# Tri-color_LED_Breakout.net
KiCad netlist of a schematic drawn in EAGLE
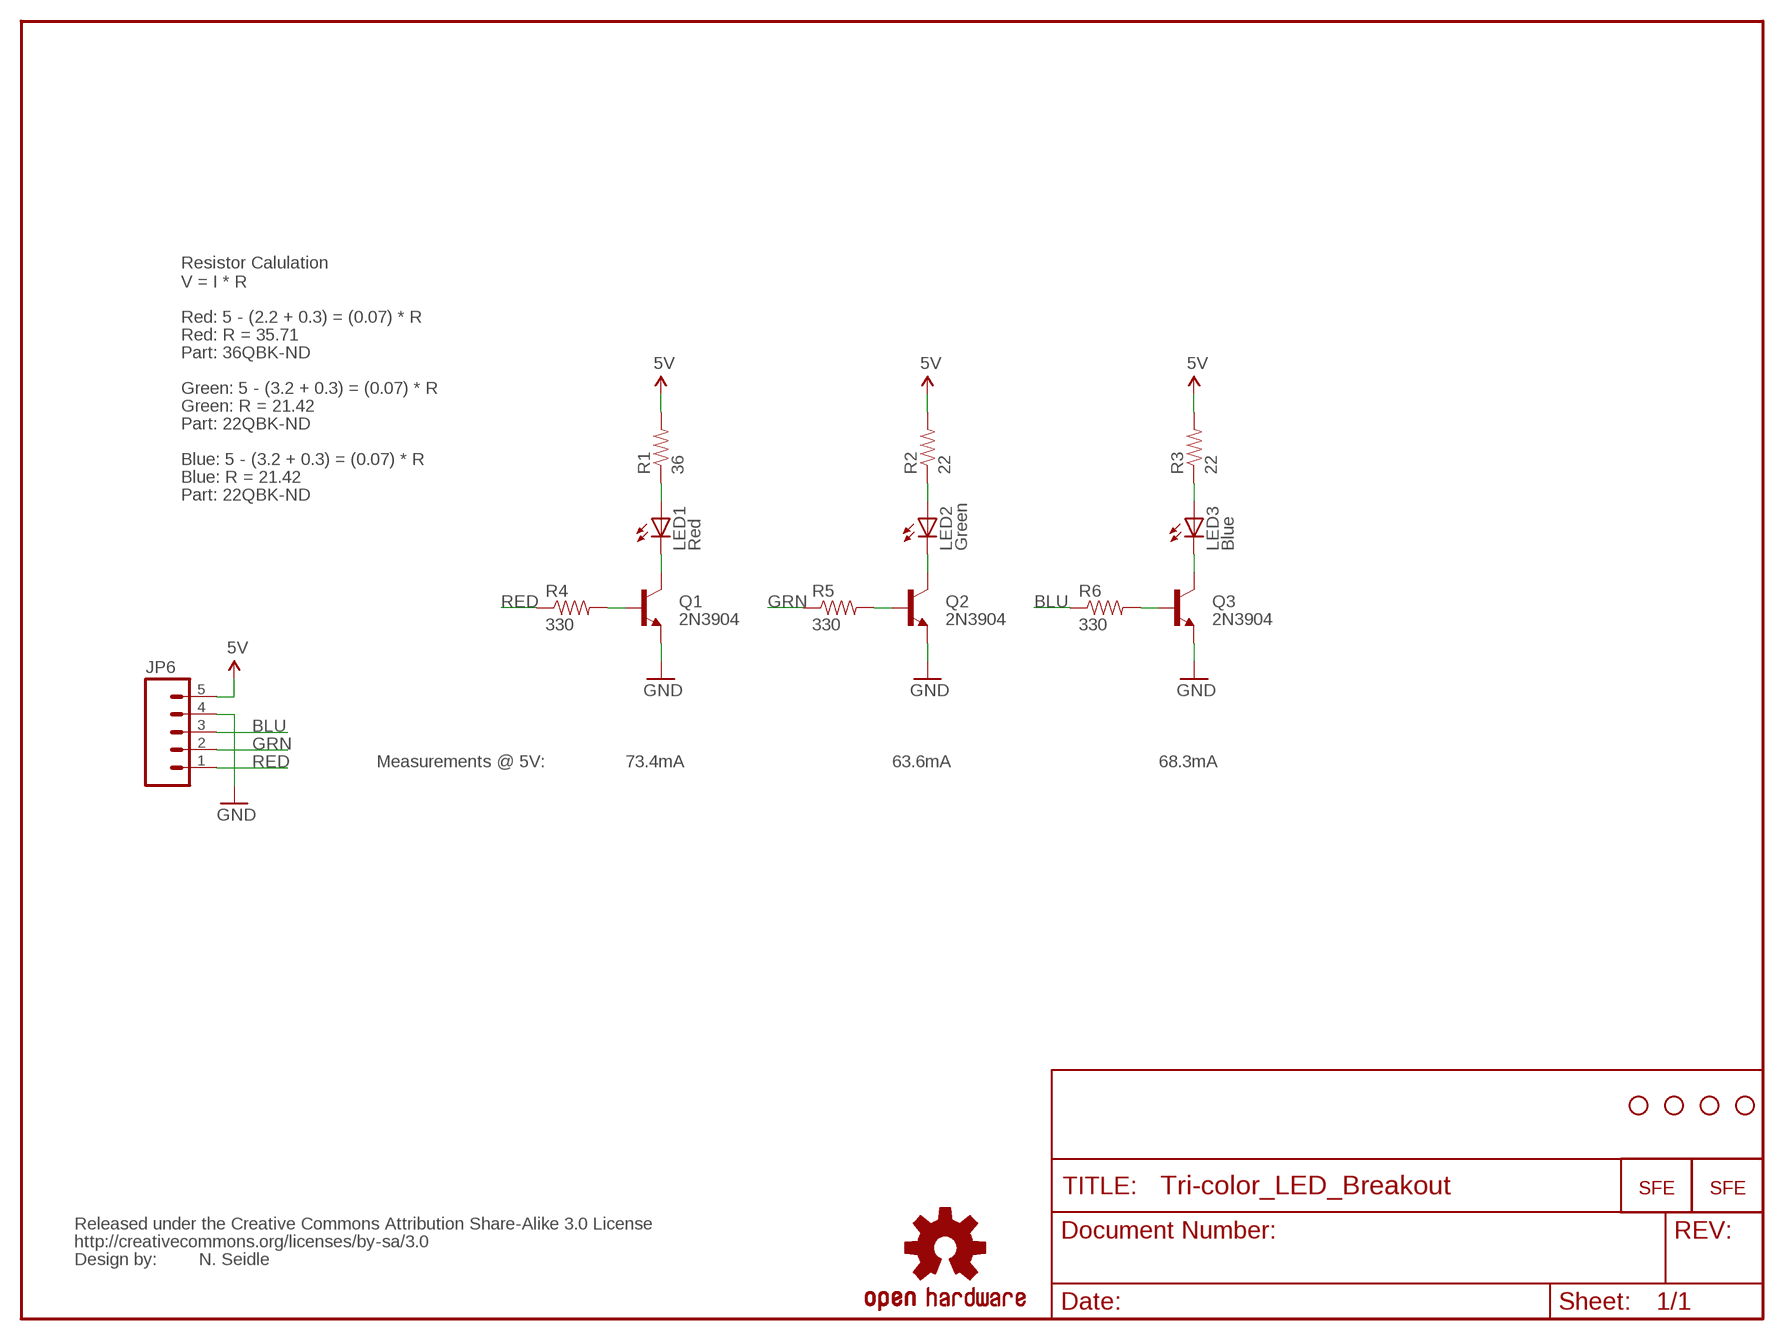
[diagram p0: schematic, sheet 1]

(export (version "E")
  (design (tool "Eeschema 10.0.6"))
  (components
    (comp (ref "JP1")
      (value "STAND-OFF")
      (footprint "eagle-import:STAND-OFF")
      (libsource (lib "eagle-import") (part "STAND-OFF"))
    )
    (comp (ref "JP2")
      (value "STAND-OFF")
      (footprint "eagle-import:STAND-OFF")
      (libsource (lib "eagle-import") (part "STAND-OFF"))
    )
    (comp (ref "JP3")
      (value "STAND-OFF")
      (footprint "eagle-import:STAND-OFF")
      (libsource (lib "eagle-import") (part "STAND-OFF"))
    )
    (comp (ref "JP4")
      (value "STAND-OFF")
      (footprint "eagle-import:STAND-OFF")
      (libsource (lib "eagle-import") (part "STAND-OFF"))
    )
    (comp (ref "JP5")
      (value "LOGO-SFESK")
      (footprint "eagle-import:SFE-LOGO-FLAME")
      (libsource (lib "eagle-import") (part "LOGO-SFESK"))
    )
    (comp (ref "JP6")
      (value "M05PTH")
      (footprint "eagle-import:1X05")
      (libsource (lib "eagle-import") (part "M05PTH"))
    )
    (comp (ref "JP7")
      (value "LOGO-SFESK")
      (footprint "eagle-import:SFE-LOGO-FLAME")
      (libsource (lib "eagle-import") (part "LOGO-SFESK"))
    )
    (comp (ref "LED1")
      (value "Red")
      (footprint "eagle-import:LED10MM")
      (libsource (lib "eagle-import") (part "LED10MM"))
    )
    (comp (ref "LED2")
      (value "Green")
      (footprint "eagle-import:LED10MM")
      (libsource (lib "eagle-import") (part "LED10MM"))
    )
    (comp (ref "LED3")
      (value "Blue")
      (footprint "eagle-import:LED10MM")
      (libsource (lib "eagle-import") (part "LED10MM"))
    )
    (comp (ref "Q1")
      (value "2N3904")
      (footprint "eagle-import:TO-92")
      (libsource (lib "eagle-import") (part "TRANSISTOR_NPNTO92"))
    )
    (comp (ref "Q2")
      (value "2N3904")
      (footprint "eagle-import:TO-92")
      (libsource (lib "eagle-import") (part "TRANSISTOR_NPNTO92"))
    )
    (comp (ref "Q3")
      (value "2N3904")
      (footprint "eagle-import:TO-92")
      (libsource (lib "eagle-import") (part "TRANSISTOR_NPNTO92"))
    )
    (comp (ref "R1")
      (value "36")
      (footprint "eagle-import:AXIAL-0.4")
      (libsource (lib "eagle-import") (part "RESISTORPTH-1/4W"))
    )
    (comp (ref "R2")
      (value "22")
      (footprint "eagle-import:AXIAL-0.4")
      (libsource (lib "eagle-import") (part "RESISTORPTH-1/4W"))
    )
    (comp (ref "R3")
      (value "22")
      (footprint "eagle-import:AXIAL-0.4")
      (libsource (lib "eagle-import") (part "RESISTORPTH-1/4W"))
    )
    (comp (ref "R4")
      (value "330")
      (footprint "eagle-import:AXIAL-0.3")
      (libsource (lib "eagle-import") (part "RESISTORAXIAL-0.3"))
    )
    (comp (ref "R5")
      (value "330")
      (footprint "eagle-import:AXIAL-0.3")
      (libsource (lib "eagle-import") (part "RESISTORAXIAL-0.3"))
    )
    (comp (ref "R6")
      (value "330")
      (footprint "eagle-import:AXIAL-0.3")
      (libsource (lib "eagle-import") (part "RESISTORAXIAL-0.3"))
    )
    (comp (ref "U$1")
      (value "CREATIVE_COMMONS")
      (footprint "eagle-import:CREATIVE_COMMONS")
      (libsource (lib "eagle-import") (part "CREATIVE_COMMONS"))
    )
    (comp (ref "U$6")
      (value "OSHW-LOGOS")
      (footprint "eagle-import:OSHW-LOGO-S")
      (libsource (lib "eagle-import") (part "OSHW-LOGOS"))
    )
  )
  (nets
    (net (code "1") (name "/BLU") (class "Default")
      (node (ref "JP6") (pin "3") (pinfunction "3_3") (pintype "passive"))
      (node (ref "R6") (pin "P$1") (pinfunction "1_P$1") (pintype "passive"))
    )
    (net (code "2") (name "/GRN") (class "Default")
      (node (ref "JP6") (pin "2") (pinfunction "2_2") (pintype "passive"))
      (node (ref "R5") (pin "P$1") (pinfunction "1_P$1") (pintype "passive"))
    )
    (net (code "3") (name "/RED") (class "Default")
      (node (ref "JP6") (pin "1") (pinfunction "1_1") (pintype "passive"))
      (node (ref "R4") (pin "P$1") (pinfunction "1_P$1") (pintype "passive"))
    )
    (net (code "4") (name "5V") (class "Default")
      (node (ref "JP6") (pin "5") (pinfunction "5_5") (pintype "passive"))
      (node (ref "R1") (pin "P$2") (pinfunction "2_P$2") (pintype "passive"))
      (node (ref "R2") (pin "P$2") (pinfunction "2_P$2") (pintype "passive"))
      (node (ref "R3") (pin "P$2") (pinfunction "2_P$2") (pintype "passive"))
    )
    (net (code "5") (name "GND") (class "Default")
      (node (ref "JP6") (pin "4") (pinfunction "4_4") (pintype "passive"))
      (node (ref "Q1") (pin "1") (pinfunction "E_1") (pintype "passive"))
      (node (ref "Q2") (pin "1") (pinfunction "E_1") (pintype "passive"))
      (node (ref "Q3") (pin "1") (pinfunction "E_1") (pintype "passive"))
    )
    (net (code "6") (name "Net-(Q1-B)") (class "Default")
      (node (ref "Q1") (pin "2") (pinfunction "B_2") (pintype "passive"))
      (node (ref "R4") (pin "P$2") (pinfunction "2_P$2") (pintype "passive"))
    )
    (net (code "7") (name "Net-(Q1-C)") (class "Default")
      (node (ref "LED1") (pin "C") (pinfunction "C_C") (pintype "passive"))
      (node (ref "Q1") (pin "3") (pinfunction "C_3") (pintype "passive"))
    )
    (net (code "8") (name "Net-(Q2-B)") (class "Default")
      (node (ref "Q2") (pin "2") (pinfunction "B_2") (pintype "passive"))
      (node (ref "R5") (pin "P$2") (pinfunction "2_P$2") (pintype "passive"))
    )
    (net (code "9") (name "Net-(Q2-C)") (class "Default")
      (node (ref "LED2") (pin "C") (pinfunction "C_C") (pintype "passive"))
      (node (ref "Q2") (pin "3") (pinfunction "C_3") (pintype "passive"))
    )
    (net (code "10") (name "Net-(Q3-B)") (class "Default")
      (node (ref "Q3") (pin "2") (pinfunction "B_2") (pintype "passive"))
      (node (ref "R6") (pin "P$2") (pinfunction "2_P$2") (pintype "passive"))
    )
    (net (code "11") (name "Net-(Q3-C)") (class "Default")
      (node (ref "LED3") (pin "C") (pinfunction "C_C") (pintype "passive"))
      (node (ref "Q3") (pin "3") (pinfunction "C_3") (pintype "passive"))
    )
    (net (code "12") (name "Net-(R1-1)") (class "Default")
      (node (ref "LED1") (pin "A") (pinfunction "A_A") (pintype "passive"))
      (node (ref "R1") (pin "P$1") (pinfunction "1_P$1") (pintype "passive"))
    )
    (net (code "13") (name "Net-(R2-1)") (class "Default")
      (node (ref "LED2") (pin "A") (pinfunction "A_A") (pintype "passive"))
      (node (ref "R2") (pin "P$1") (pinfunction "1_P$1") (pintype "passive"))
    )
    (net (code "14") (name "Net-(R3-1)") (class "Default")
      (node (ref "LED3") (pin "A") (pinfunction "A_A") (pintype "passive"))
      (node (ref "R3") (pin "P$1") (pinfunction "1_P$1") (pintype "passive"))
    )
  )
)
